# Feinstaubsensor_w.net
KiCad netlist of a schematic drawn in EAGLE
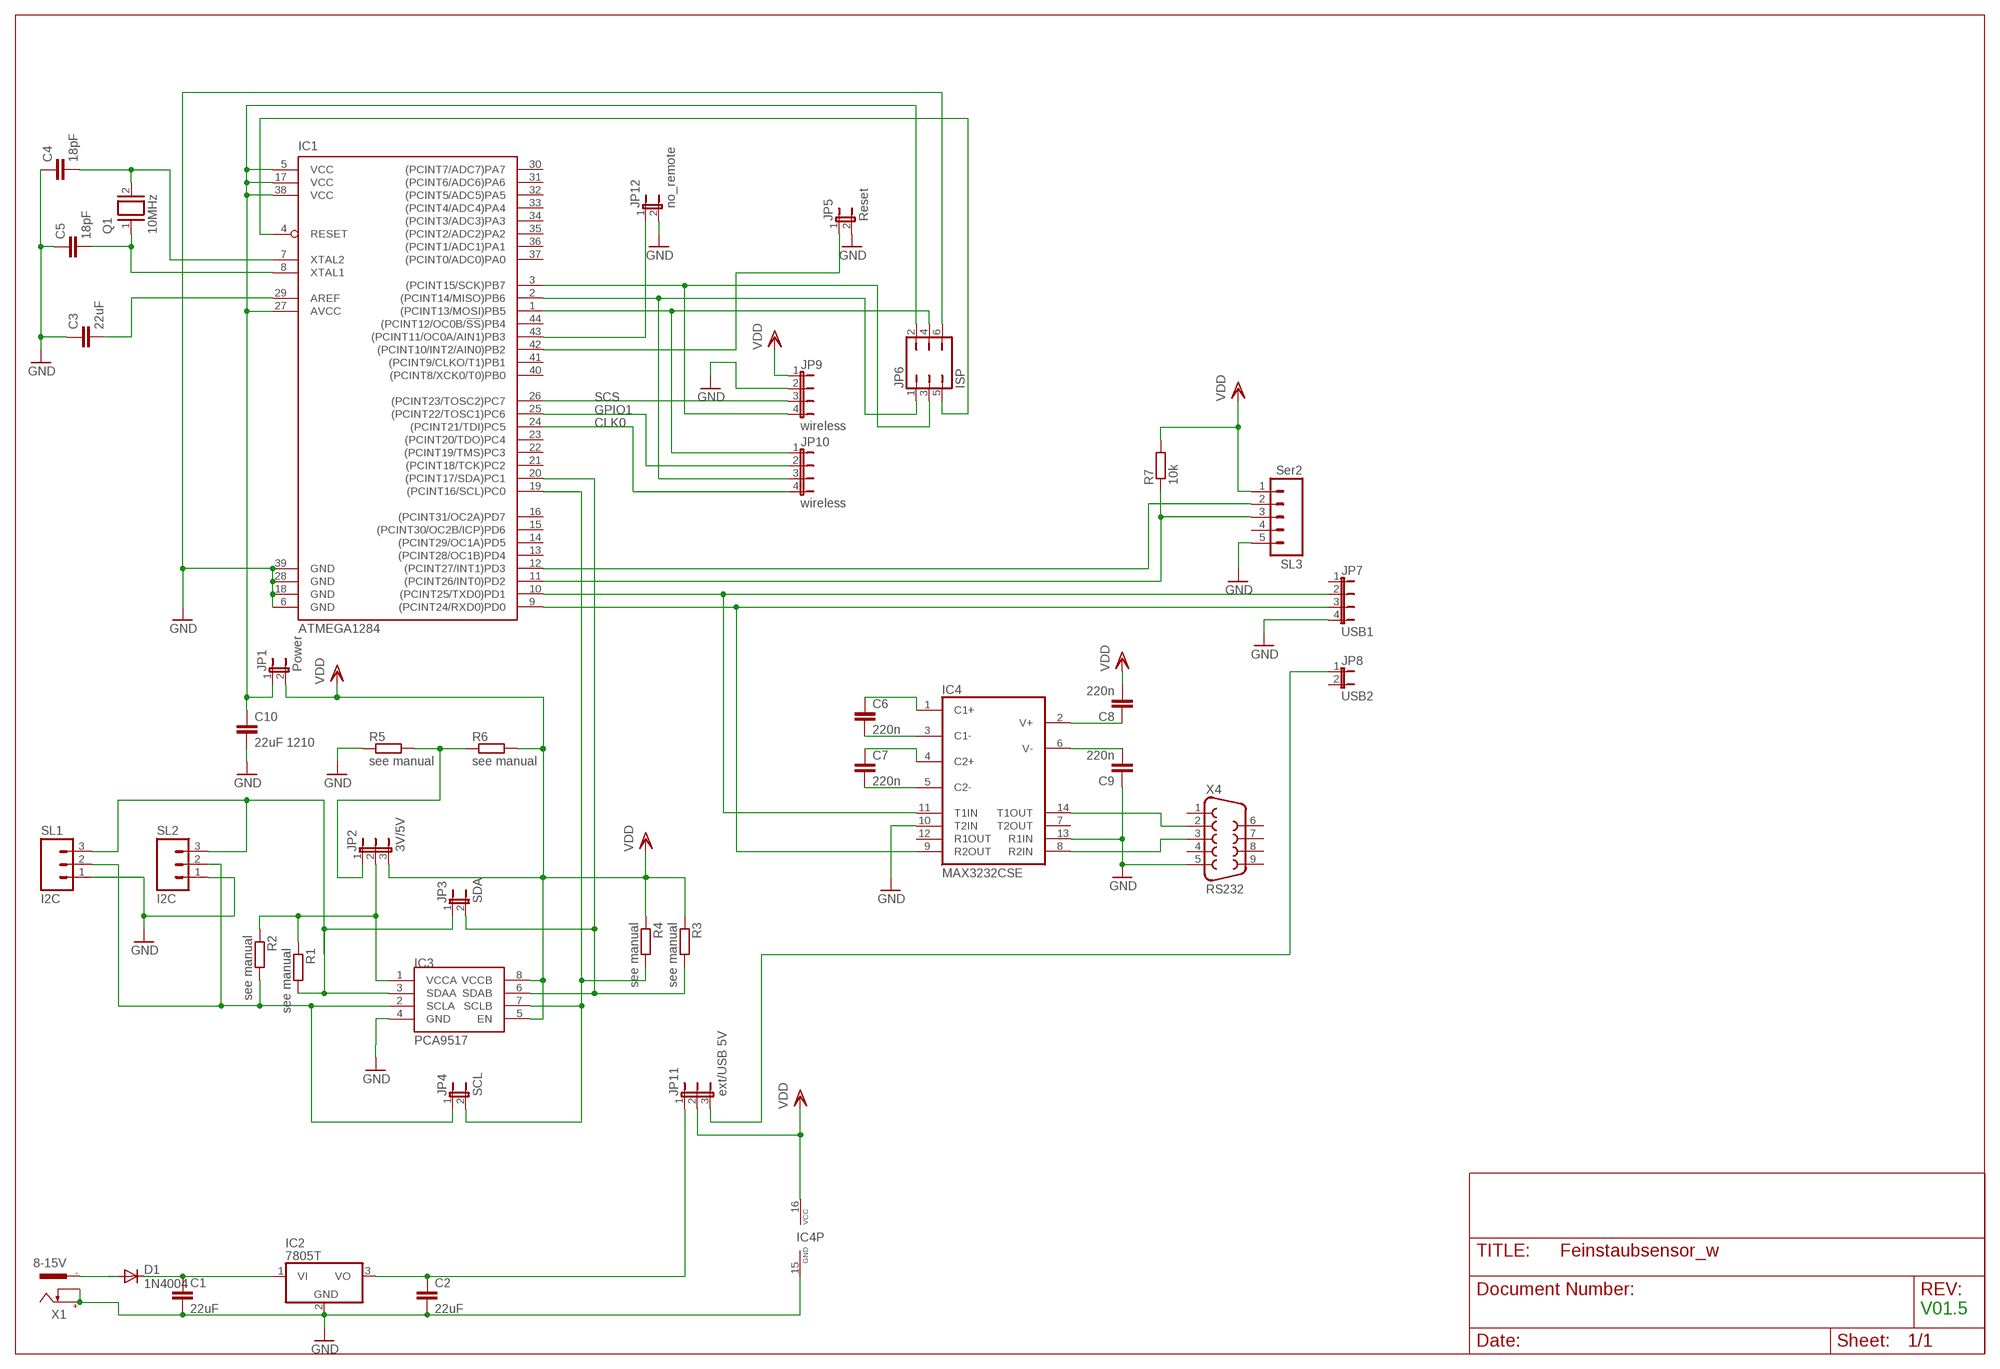
[diagram p0: schematic, sheet 1]

(export (version "E")
  (design (tool "Eeschema 10.0.6"))
  (components
    (comp (ref "C1")
      (value "22uF")
      (footprint "eagle-import:C1206")
      (libsource (lib "eagle-import") (part "C-EUC1206"))
    )
    (comp (ref "C2")
      (value "22uF")
      (footprint "eagle-import:C1206")
      (libsource (lib "eagle-import") (part "C-EUC1206"))
    )
    (comp (ref "C3")
      (value "22uF")
      (footprint "eagle-import:C1206")
      (libsource (lib "eagle-import") (part "C-EUC1206"))
    )
    (comp (ref "C4")
      (value "18pF")
      (footprint "eagle-import:C025-025X050")
      (libsource (lib "eagle-import") (part "resistor_C-EU025-025X050"))
    )
    (comp (ref "C5")
      (value "18pF")
      (footprint "eagle-import:C025-025X050")
      (libsource (lib "eagle-import") (part "resistor_C-EU025-025X050"))
    )
    (comp (ref "C6")
      (value "220n")
      (footprint "eagle-import:C1206")
      (libsource (lib "eagle-import") (part "C-EUC1206"))
    )
    (comp (ref "C7")
      (value "220n")
      (footprint "eagle-import:C1206")
      (libsource (lib "eagle-import") (part "C-EUC1206"))
    )
    (comp (ref "C8")
      (value "220n")
      (footprint "eagle-import:C1206")
      (libsource (lib "eagle-import") (part "C-EUC1206"))
    )
    (comp (ref "C9")
      (value "220n")
      (footprint "eagle-import:C1206")
      (libsource (lib "eagle-import") (part "C-EUC1206"))
    )
    (comp (ref "C10")
      (value "22uF 1210")
      (footprint "eagle-import:C1206")
      (libsource (lib "eagle-import") (part "C-EUC1206"))
    )
    (comp (ref "D1")
      (value "1N4004")
      (footprint "eagle-import:DO41-10")
      (libsource (lib "eagle-import") (part "1N4004"))
    )
    (comp (ref "IC1")
      (value "ATMEGA1284")
      (footprint "eagle-import:TQFP44")
      (fields (field (name "MPN") "ATMEGA644PV-10AU"))
      (libsource (lib "eagle-import") (part "ATMEGA644A"))
    )
    (comp (ref "IC2")
      (value "7805T")
      (footprint "eagle-import:TO220H")
      (libsource (lib "eagle-import") (part "78T05"))
    )
    (comp (ref "IC3")
      (value "PCA9517")
      (footprint "eagle-import:SO-08")
      (libsource (lib "eagle-import") (part "PCA9517"))
    )
    (comp (ref "IC4")
      (value "MAX3232CSE")
      (footprint "eagle-import:SO16")
      (libsource (lib "eagle-import") (part "MAX3232SEC"))
    )
    (comp (ref "JP1")
      (value "Power")
      (footprint "eagle-import:JP1")
      (libsource (lib "eagle-import") (part "JP1E"))
    )
    (comp (ref "JP2")
      (value "3V/5V")
      (footprint "eagle-import:JP2")
      (libsource (lib "eagle-import") (part "JP2E"))
    )
    (comp (ref "JP3")
      (value "SDA")
      (footprint "eagle-import:JP1")
      (libsource (lib "eagle-import") (part "JP1E"))
    )
    (comp (ref "JP4")
      (value "SCL")
      (footprint "eagle-import:JP1")
      (libsource (lib "eagle-import") (part "JP1E"))
    )
    (comp (ref "JP5")
      (value "Reset")
      (footprint "eagle-import:JP1")
      (libsource (lib "eagle-import") (part "JP1E"))
    )
    (comp (ref "JP6")
      (value "ISP")
      (footprint "eagle-import:JP3Q")
      (libsource (lib "eagle-import") (part "JP3Q"))
    )
    (comp (ref "JP7")
      (value "USB1")
      (footprint "eagle-import:JP4")
      (libsource (lib "eagle-import") (part "JP4E"))
    )
    (comp (ref "JP8")
      (value "USB2")
      (footprint "eagle-import:JP1")
      (libsource (lib "eagle-import") (part "JP1E"))
    )
    (comp (ref "JP9")
      (value "wireless")
      (footprint "eagle-import:JP4")
      (libsource (lib "eagle-import") (part "JP4E"))
    )
    (comp (ref "JP10")
      (value "wireless")
      (footprint "eagle-import:JP4")
      (libsource (lib "eagle-import") (part "JP4E"))
    )
    (comp (ref "JP11")
      (value "ext/USB 5V")
      (footprint "eagle-import:JP2")
      (libsource (lib "eagle-import") (part "JP2E"))
    )
    (comp (ref "JP12")
      (value "no_remote")
      (footprint "eagle-import:JP1")
      (libsource (lib "eagle-import") (part "JP1E"))
    )
    (comp (ref "Q1")
      (value "10MHz")
      (footprint "eagle-import:QS")
      (libsource (lib "eagle-import") (part "XTAL/S"))
    )
    (comp (ref "R1")
      (value "see manual")
      (footprint "eagle-import:R1206")
      (libsource (lib "eagle-import") (part "R-EU_R1206"))
    )
    (comp (ref "R2")
      (value "see manual")
      (footprint "eagle-import:R1206")
      (libsource (lib "eagle-import") (part "R-EU_R1206"))
    )
    (comp (ref "R3")
      (value "see manual")
      (footprint "eagle-import:R1206")
      (libsource (lib "eagle-import") (part "R-EU_R1206"))
    )
    (comp (ref "R4")
      (value "see manual")
      (footprint "eagle-import:R1206")
      (libsource (lib "eagle-import") (part "R-EU_R1206"))
    )
    (comp (ref "R5")
      (value "see manual")
      (footprint "eagle-import:R1206")
      (libsource (lib "eagle-import") (part "R-EU_R1206"))
    )
    (comp (ref "R6")
      (value "see manual")
      (footprint "eagle-import:R1206")
      (libsource (lib "eagle-import") (part "R-EU_R1206"))
    )
    (comp (ref "R7")
      (value "10k")
      (footprint "eagle-import:R1206")
      (libsource (lib "eagle-import") (part "R-EU_R1206"))
    )
    (comp (ref "SL1")
      (value "I2C")
      (footprint "eagle-import:03P")
      (libsource (lib "eagle-import") (part "M03"))
    )
    (comp (ref "SL2")
      (value "I2C")
      (footprint "eagle-import:03P")
      (libsource (lib "eagle-import") (part "M03"))
    )
    (comp (ref "SL3")
      (value "Ser2")
      (footprint "eagle-import:05P")
      (libsource (lib "eagle-import") (part "M05"))
    )
    (comp (ref "X1")
      (value "8-15V")
      (footprint "eagle-import:737992-5")
      (libsource (lib "eagle-import") (part "737992-55"))
    )
    (comp (ref "X4")
      (value "RS232")
      (footprint "eagle-import:F09H")
      (libsource (lib "eagle-import") (part "F09H"))
    )
  )
  (nets
    (net (code "1") (name "/CLK0") (class "Default")
      (node (ref "IC1") (pin "24") (pinfunction "(PCINT21/TDI)PC5_24") (pintype "output"))
      (node (ref "JP10") (pin "4") (pinfunction "4_4") (pintype "passive"))
    )
    (net (code "2") (name "/GPIO1") (class "Default")
      (node (ref "IC1") (pin "25") (pinfunction "(PCINT22/TOSC1)PC6_25") (pintype "output"))
      (node (ref "JP10") (pin "2") (pinfunction "2_2") (pintype "passive"))
    )
    (net (code "3") (name "/SCS") (class "Default")
      (node (ref "IC1") (pin "26") (pinfunction "(PCINT23/TOSC2)PC7_26") (pintype "output"))
      (node (ref "JP9") (pin "3") (pinfunction "3_3") (pintype "passive"))
    )
    (net (code "4") (name "GND") (class "Default")
      (node (ref "C1") (pin "2") (pinfunction "2_2") (pintype "passive"))
      (node (ref "C10") (pin "2") (pinfunction "2_2") (pintype "passive"))
      (node (ref "C2") (pin "2") (pinfunction "2_2") (pintype "passive"))
      (node (ref "C3") (pin "1") (pinfunction "1_1") (pintype "passive"))
      (node (ref "C4") (pin "1") (pinfunction "1_1") (pintype "passive"))
      (node (ref "C5") (pin "1") (pinfunction "1_1") (pintype "passive"))
      (node (ref "C9") (pin "1") (pinfunction "1_1") (pintype "passive"))
      (node (ref "IC1") (pin "18") (pinfunction "GND_18") (pintype "power_in"))
      (node (ref "IC1") (pin "28") (pinfunction "GND_28") (pintype "power_in"))
      (node (ref "IC1") (pin "39") (pinfunction "GND_39") (pintype "power_in"))
      (node (ref "IC1") (pin "6") (pinfunction "GND_6") (pintype "power_in"))
      (node (ref "IC2") (pin "2") (pinfunction "GND_2") (pintype "passive"))
      (node (ref "IC3") (pin "4") (pinfunction "GND_4") (pintype "bidirectional"))
      (node (ref "IC4") (pin "10") (pinfunction "T2IN_10") (pintype "input"))
      (node (ref "IC4") (pin "13") (pinfunction "R1IN_13") (pintype "input"))
      (node (ref "IC4") (pin "15") (pinfunction "GND_15") (pintype "power_in"))
      (node (ref "JP12") (pin "2") (pinfunction "2_2") (pintype "passive"))
      (node (ref "JP5") (pin "2") (pinfunction "2_2") (pintype "passive"))
      (node (ref "JP6") (pin "6") (pinfunction "6_6") (pintype "passive"))
      (node (ref "JP7") (pin "4") (pinfunction "4_4") (pintype "passive"))
      (node (ref "JP9") (pin "2") (pinfunction "2_2") (pintype "passive"))
      (node (ref "R5") (pin "1") (pinfunction "1_1") (pintype "passive"))
      (node (ref "SL1") (pin "1") (pinfunction "1_1") (pintype "passive"))
      (node (ref "SL2") (pin "1") (pinfunction "1_1") (pintype "passive"))
      (node (ref "SL3") (pin "5") (pinfunction "5_5") (pintype "passive"))
      (node (ref "X1") (pin "+") (pinfunction "+_+") (pintype "passive"))
      (node (ref "X1") (pin "K") (pinfunction "K_K") (pintype "passive"))
      (node (ref "X4") (pin "5") (pinfunction "5_5") (pintype "passive"))
    )
    (net (code "5") (name "Net-(D1-PadA)") (class "Default")
      (node (ref "D1") (pin "A") (pinfunction "A_A") (pintype "passive"))
      (node (ref "X1") (pin "-1") (pinfunction "-1_-1") (pintype "passive"))
    )
    (net (code "6") (name "Net-(IC1-(PCINT10{slash}INT2{slash}AIN0)PB2)") (class "Default")
      (node (ref "IC1") (pin "42") (pinfunction "(PCINT10/INT2/AIN0)PB2_42") (pintype "bidirectional"))
      (node (ref "JP5") (pin "1") (pinfunction "1_1") (pintype "passive"))
    )
    (net (code "7") (name "Net-(IC1-(PCINT11{slash}OC0A{slash}AIN1)PB3)") (class "Default")
      (node (ref "IC1") (pin "43") (pinfunction "(PCINT11/OC0A/AIN1)PB3_43") (pintype "bidirectional"))
      (node (ref "JP12") (pin "1") (pinfunction "1_1") (pintype "passive"))
    )
    (net (code "8") (name "Net-(IC1-(PCINT13{slash}MOSI)PB5)") (class "Default")
      (node (ref "IC1") (pin "1") (pinfunction "(PCINT13/MOSI)PB5_1") (pintype "bidirectional"))
      (node (ref "JP10") (pin "1") (pinfunction "1_1") (pintype "passive"))
      (node (ref "JP6") (pin "4") (pinfunction "4_4") (pintype "passive"))
    )
    (net (code "9") (name "Net-(IC1-(PCINT14{slash}MISO)PB6)") (class "Default")
      (node (ref "IC1") (pin "2") (pinfunction "(PCINT14/MISO)PB6_2") (pintype "bidirectional"))
      (node (ref "JP10") (pin "3") (pinfunction "3_3") (pintype "passive"))
      (node (ref "JP6") (pin "1") (pinfunction "1_1") (pintype "passive"))
    )
    (net (code "10") (name "Net-(IC1-(PCINT15{slash}SCK)PB7)") (class "Default")
      (node (ref "IC1") (pin "3") (pinfunction "(PCINT15/SCK)PB7_3") (pintype "bidirectional"))
      (node (ref "JP6") (pin "3") (pinfunction "3_3") (pintype "passive"))
      (node (ref "JP9") (pin "4") (pinfunction "4_4") (pintype "passive"))
    )
    (net (code "11") (name "Net-(IC1-(PCINT16{slash}SCL)PC0)") (class "Default")
      (node (ref "IC1") (pin "19") (pinfunction "(PCINT16/SCL)PC0_19") (pintype "output"))
      (node (ref "IC3") (pin "7") (pinfunction "SCLB_7") (pintype "bidirectional"))
      (node (ref "JP4") (pin "2") (pinfunction "2_2") (pintype "passive"))
      (node (ref "R4") (pin "2") (pinfunction "2_2") (pintype "passive"))
    )
    (net (code "12") (name "Net-(IC1-(PCINT17{slash}SDA)PC1)") (class "Default")
      (node (ref "IC1") (pin "20") (pinfunction "(PCINT17/SDA)PC1_20") (pintype "output"))
      (node (ref "IC3") (pin "6") (pinfunction "SDAB_6") (pintype "bidirectional"))
      (node (ref "JP3") (pin "2") (pinfunction "2_2") (pintype "passive"))
      (node (ref "R3") (pin "2") (pinfunction "2_2") (pintype "passive"))
    )
    (net (code "13") (name "Net-(IC1-(PCINT24{slash}RXD0)PD0)") (class "Default")
      (node (ref "IC1") (pin "9") (pinfunction "(PCINT24/RXD0)PD0_9") (pintype "bidirectional"))
      (node (ref "IC4") (pin "9") (pinfunction "R2OUT_9") (pintype "output"))
      (node (ref "JP7") (pin "3") (pinfunction "3_3") (pintype "passive"))
    )
    (net (code "14") (name "Net-(IC1-(PCINT25{slash}TXD0)PD1)") (class "Default")
      (node (ref "IC1") (pin "10") (pinfunction "(PCINT25/TXD0)PD1_10") (pintype "bidirectional"))
      (node (ref "IC4") (pin "11") (pinfunction "T1IN_11") (pintype "input"))
      (node (ref "JP7") (pin "2") (pinfunction "2_2") (pintype "passive"))
    )
    (net (code "15") (name "Net-(IC1-(PCINT26{slash}INT0)PD2)") (class "Default")
      (node (ref "IC1") (pin "11") (pinfunction "(PCINT26/INT0)PD2_11") (pintype "bidirectional"))
      (node (ref "R7") (pin "1") (pinfunction "1_1") (pintype "passive"))
      (node (ref "SL3") (pin "3") (pinfunction "3_3") (pintype "passive"))
    )
    (net (code "16") (name "Net-(IC1-(PCINT27{slash}INT1)PD3)") (class "Default")
      (node (ref "IC1") (pin "12") (pinfunction "(PCINT27/INT1)PD3_12") (pintype "bidirectional"))
      (node (ref "SL3") (pin "2") (pinfunction "2_2") (pintype "passive"))
    )
    (net (code "17") (name "Net-(IC1-AREF)") (class "Default")
      (node (ref "C3") (pin "2") (pinfunction "2_2") (pintype "passive"))
      (node (ref "IC1") (pin "29") (pinfunction "AREF_29") (pintype "passive"))
    )
    (net (code "18") (name "Net-(IC1-AVCC)") (class "Default")
      (node (ref "C10") (pin "1") (pinfunction "1_1") (pintype "passive"))
      (node (ref "IC1") (pin "17") (pinfunction "VCC_17") (pintype "power_in"))
      (node (ref "IC1") (pin "27") (pinfunction "AVCC_27") (pintype "power_in"))
      (node (ref "IC1") (pin "38") (pinfunction "VCC_38") (pintype "power_in"))
      (node (ref "IC1") (pin "5") (pinfunction "VCC_5") (pintype "power_in"))
      (node (ref "JP1") (pin "1") (pinfunction "1_1") (pintype "passive"))
      (node (ref "JP6") (pin "2") (pinfunction "2_2") (pintype "passive"))
    )
    (net (code "19") (name "Net-(IC1-RESET)") (class "Default")
      (node (ref "IC1") (pin "4") (pinfunction "RESET_4") (pintype "input"))
      (node (ref "JP6") (pin "5") (pinfunction "5_5") (pintype "passive"))
    )
    (net (code "20") (name "Net-(IC1-XTAL1)") (class "Default")
      (node (ref "C5") (pin "2") (pinfunction "2_2") (pintype "passive"))
      (node (ref "IC1") (pin "8") (pinfunction "XTAL1_8") (pintype "bidirectional"))
      (node (ref "Q1") (pin "1") (pinfunction "1_1") (pintype "passive"))
    )
    (net (code "21") (name "Net-(IC1-XTAL2)") (class "Default")
      (node (ref "C4") (pin "2") (pinfunction "2_2") (pintype "passive"))
      (node (ref "IC1") (pin "7") (pinfunction "XTAL2_7") (pintype "bidirectional"))
      (node (ref "Q1") (pin "2") (pinfunction "2_2") (pintype "passive"))
    )
    (net (code "22") (name "Net-(IC2-VI)") (class "Default")
      (node (ref "C1") (pin "1") (pinfunction "1_1") (pintype "passive"))
      (node (ref "D1") (pin "C") (pinfunction "C_C") (pintype "passive"))
      (node (ref "IC2") (pin "1") (pinfunction "VI_1") (pintype "input"))
    )
    (net (code "23") (name "Net-(IC2-VO)") (class "Default")
      (node (ref "C2") (pin "1") (pinfunction "1_1") (pintype "passive"))
      (node (ref "IC2") (pin "3") (pinfunction "VO_3") (pintype "passive"))
      (node (ref "JP11") (pin "1") (pinfunction "1_1") (pintype "passive"))
    )
    (net (code "24") (name "Net-(IC3-SCLA)") (class "Default")
      (node (ref "IC3") (pin "2") (pinfunction "SCLA_2") (pintype "bidirectional"))
      (node (ref "JP4") (pin "1") (pinfunction "1_1") (pintype "passive"))
      (node (ref "R2") (pin "2") (pinfunction "2_2") (pintype "passive"))
      (node (ref "SL1") (pin "2") (pinfunction "2_2") (pintype "passive"))
      (node (ref "SL2") (pin "2") (pinfunction "2_2") (pintype "passive"))
    )
    (net (code "25") (name "Net-(IC3-SDAA)") (class "Default")
      (node (ref "IC3") (pin "3") (pinfunction "SDAA_3") (pintype "bidirectional"))
      (node (ref "JP3") (pin "1") (pinfunction "1_1") (pintype "passive"))
      (node (ref "R1") (pin "2") (pinfunction "2_2") (pintype "passive"))
      (node (ref "SL1") (pin "3") (pinfunction "3_3") (pintype "passive"))
      (node (ref "SL2") (pin "3") (pinfunction "3_3") (pintype "passive"))
    )
    (net (code "26") (name "Net-(IC3-VCCA)") (class "Default")
      (node (ref "IC3") (pin "1") (pinfunction "VCCA_1") (pintype "bidirectional"))
      (node (ref "JP2") (pin "2") (pinfunction "2_2") (pintype "passive"))
      (node (ref "R1") (pin "1") (pinfunction "1_1") (pintype "passive"))
      (node (ref "R2") (pin "1") (pinfunction "1_1") (pintype "passive"))
    )
    (net (code "27") (name "Net-(IC4A-C1+)") (class "Default")
      (node (ref "C6") (pin "1") (pinfunction "1_1") (pintype "passive"))
      (node (ref "IC4") (pin "1") (pinfunction "C1+_1") (pintype "bidirectional"))
    )
    (net (code "28") (name "Net-(IC4A-C1-)") (class "Default")
      (node (ref "C6") (pin "2") (pinfunction "2_2") (pintype "passive"))
      (node (ref "IC4") (pin "3") (pinfunction "C1-_3") (pintype "bidirectional"))
    )
    (net (code "29") (name "Net-(IC4A-C2+)") (class "Default")
      (node (ref "C7") (pin "1") (pinfunction "1_1") (pintype "passive"))
      (node (ref "IC4") (pin "4") (pinfunction "C2+_4") (pintype "bidirectional"))
    )
    (net (code "30") (name "Net-(IC4A-C2-)") (class "Default")
      (node (ref "C7") (pin "2") (pinfunction "2_2") (pintype "passive"))
      (node (ref "IC4") (pin "5") (pinfunction "C2-_5") (pintype "bidirectional"))
    )
    (net (code "31") (name "Net-(IC4A-R2IN)") (class "Default")
      (node (ref "IC4") (pin "8") (pinfunction "R2IN_8") (pintype "input"))
      (node (ref "X4") (pin "3") (pinfunction "3_3") (pintype "passive"))
    )
    (net (code "32") (name "Net-(IC4A-T1OUT)") (class "Default")
      (node (ref "IC4") (pin "14") (pinfunction "T1OUT_14") (pintype "output"))
      (node (ref "X4") (pin "2") (pinfunction "2_2") (pintype "passive"))
    )
    (net (code "33") (name "Net-(IC4A-V+)") (class "Default")
      (node (ref "C8") (pin "1") (pinfunction "1_1") (pintype "passive"))
      (node (ref "IC4") (pin "2") (pinfunction "V+_2") (pintype "bidirectional"))
    )
    (net (code "34") (name "Net-(IC4A-V-)") (class "Default")
      (node (ref "C9") (pin "2") (pinfunction "2_2") (pintype "passive"))
      (node (ref "IC4") (pin "6") (pinfunction "V-_6") (pintype "bidirectional"))
    )
    (net (code "35") (name "Net-(JP2-Pad1)") (class "Default")
      (node (ref "JP2") (pin "1") (pinfunction "1_1") (pintype "passive"))
      (node (ref "R5") (pin "2") (pinfunction "2_2") (pintype "passive"))
      (node (ref "R6") (pin "1") (pinfunction "1_1") (pintype "passive"))
    )
    (net (code "36") (name "Net-(JP11-Pad3)") (class "Default")
      (node (ref "JP11") (pin "3") (pinfunction "3_3") (pintype "passive"))
      (node (ref "JP8") (pin "1") (pinfunction "1_1") (pintype "passive"))
    )
    (net (code "37") (name "VDD") (class "Default")
      (node (ref "C8") (pin "2") (pinfunction "2_2") (pintype "passive"))
      (node (ref "IC3") (pin "5") (pinfunction "EN_5") (pintype "bidirectional"))
      (node (ref "IC3") (pin "8") (pinfunction "VCCB_8") (pintype "bidirectional"))
      (node (ref "IC4") (pin "16") (pinfunction "VCC_16") (pintype "power_in"))
      (node (ref "JP1") (pin "2") (pinfunction "2_2") (pintype "passive"))
      (node (ref "JP11") (pin "2") (pinfunction "2_2") (pintype "passive"))
      (node (ref "JP2") (pin "3") (pinfunction "3_3") (pintype "passive"))
      (node (ref "JP9") (pin "1") (pinfunction "1_1") (pintype "passive"))
      (node (ref "R3") (pin "1") (pinfunction "1_1") (pintype "passive"))
      (node (ref "R4") (pin "1") (pinfunction "1_1") (pintype "passive"))
      (node (ref "R6") (pin "2") (pinfunction "2_2") (pintype "passive"))
      (node (ref "R7") (pin "2") (pinfunction "2_2") (pintype "passive"))
      (node (ref "SL3") (pin "1") (pinfunction "1_1") (pintype "passive"))
    )
    (net (code "38") (name "unconnected-(IC1-(PCINT0{slash}ADC0)PA0-Pad37)") (class "Default")
      (node (ref "IC1") (pin "37") (pinfunction "(PCINT0/ADC0)PA0_37") (pintype "bidirectional"))
    )
    (net (code "39") (name "unconnected-(IC1-(PCINT1{slash}ADC1)PA1-Pad36)") (class "Default")
      (node (ref "IC1") (pin "36") (pinfunction "(PCINT1/ADC1)PA1_36") (pintype "bidirectional"))
    )
    (net (code "40") (name "unconnected-(IC1-(PCINT2{slash}ADC2)PA2-Pad35)") (class "Default")
      (node (ref "IC1") (pin "35") (pinfunction "(PCINT2/ADC2)PA2_35") (pintype "bidirectional"))
    )
    (net (code "41") (name "unconnected-(IC1-(PCINT3{slash}ADC3)PA3-Pad34)") (class "Default")
      (node (ref "IC1") (pin "34") (pinfunction "(PCINT3/ADC3)PA3_34") (pintype "bidirectional"))
    )
    (net (code "42") (name "unconnected-(IC1-(PCINT4{slash}ADC4)PA4-Pad33)") (class "Default")
      (node (ref "IC1") (pin "33") (pinfunction "(PCINT4/ADC4)PA4_33") (pintype "bidirectional"))
    )
    (net (code "43") (name "unconnected-(IC1-(PCINT5{slash}ADC5)PA5-Pad32)") (class "Default")
      (node (ref "IC1") (pin "32") (pinfunction "(PCINT5/ADC5)PA5_32") (pintype "bidirectional"))
    )
    (net (code "44") (name "unconnected-(IC1-(PCINT6{slash}ADC6)PA6-Pad31)") (class "Default")
      (node (ref "IC1") (pin "31") (pinfunction "(PCINT6/ADC6)PA6_31") (pintype "bidirectional"))
    )
    (net (code "45") (name "unconnected-(IC1-(PCINT7{slash}ADC7)PA7-Pad30)") (class "Default")
      (node (ref "IC1") (pin "30") (pinfunction "(PCINT7/ADC7)PA7_30") (pintype "bidirectional"))
    )
    (net (code "46") (name "unconnected-(IC1-(PCINT8{slash}XCK0{slash}T0)PB0-Pad40)") (class "Default")
      (node (ref "IC1") (pin "40") (pinfunction "(PCINT8/XCK0/T0)PB0_40") (pintype "bidirectional"))
    )
    (net (code "47") (name "unconnected-(IC1-(PCINT9{slash}CLKO{slash}T1)PB1-Pad41)") (class "Default")
      (node (ref "IC1") (pin "41") (pinfunction "(PCINT9/CLKO/T1)PB1_41") (pintype "bidirectional"))
    )
    (net (code "48") (name "unconnected-(IC1-(PCINT12{slash}OC0B{slash}~{SS})PB4-Pad44)") (class "Default")
      (node (ref "IC1") (pin "44") (pinfunction "(PCINT12/OC0B/~{SS})PB4_44") (pintype "bidirectional"))
    )
    (net (code "49") (name "unconnected-(IC1-(PCINT18{slash}TCK)PC2-Pad21)") (class "Default")
      (node (ref "IC1") (pin "21") (pinfunction "(PCINT18/TCK)PC2_21") (pintype "output"))
    )
    (net (code "50") (name "unconnected-(IC1-(PCINT19{slash}TMS)PC3-Pad22)") (class "Default")
      (node (ref "IC1") (pin "22") (pinfunction "(PCINT19/TMS)PC3_22") (pintype "output"))
    )
    (net (code "51") (name "unconnected-(IC1-(PCINT20{slash}TDO)PC4-Pad23)") (class "Default")
      (node (ref "IC1") (pin "23") (pinfunction "(PCINT20/TDO)PC4_23") (pintype "output"))
    )
    (net (code "52") (name "unconnected-(IC1-(PCINT28{slash}OC1B)PD4-Pad13)") (class "Default")
      (node (ref "IC1") (pin "13") (pinfunction "(PCINT28/OC1B)PD4_13") (pintype "bidirectional"))
    )
    (net (code "53") (name "unconnected-(IC1-(PCINT29{slash}OC1A)PD5-Pad14)") (class "Default")
      (node (ref "IC1") (pin "14") (pinfunction "(PCINT29/OC1A)PD5_14") (pintype "bidirectional"))
    )
    (net (code "54") (name "unconnected-(IC1-(PCINT30{slash}OC2B{slash}ICP)PD6-Pad15)") (class "Default")
      (node (ref "IC1") (pin "15") (pinfunction "(PCINT30/OC2B/ICP)PD6_15") (pintype "bidirectional"))
    )
    (net (code "55") (name "unconnected-(IC1-(PCINT31{slash}OC2A)PD7-Pad16)") (class "Default")
      (node (ref "IC1") (pin "16") (pinfunction "(PCINT31/OC2A)PD7_16") (pintype "bidirectional"))
    )
    (net (code "56") (name "unconnected-(IC4A-R1OUT-Pad12)") (class "Default")
      (node (ref "IC4") (pin "12") (pinfunction "R1OUT_12") (pintype "output"))
    )
    (net (code "57") (name "unconnected-(IC4A-T2OUT-Pad7)") (class "Default")
      (node (ref "IC4") (pin "7") (pinfunction "T2OUT_7") (pintype "output"))
    )
    (net (code "58") (name "unconnected-(JP7-Pad1)") (class "Default")
      (node (ref "JP7") (pin "1") (pinfunction "1_1") (pintype "passive"))
    )
    (net (code "59") (name "unconnected-(JP8-Pad2)") (class "Default")
      (node (ref "JP8") (pin "2") (pinfunction "2_2") (pintype "passive"))
    )
    (net (code "60") (name "unconnected-(SL3-Pad4)") (class "Default")
      (node (ref "SL3") (pin "4") (pinfunction "4_4") (pintype "passive"))
    )
    (net (code "61") (name "unconnected-(X1-Pad-2)") (class "Default")
      (node (ref "X1") (pin "-2") (pinfunction "-2_-2") (pintype "passive"))
    )
    (net (code "62") (name "unconnected-(X4-Pad1)") (class "Default")
      (node (ref "X4") (pin "1") (pinfunction "1_1") (pintype "passive"))
    )
    (net (code "63") (name "unconnected-(X4-Pad4)") (class "Default")
      (node (ref "X4") (pin "4") (pinfunction "4_4") (pintype "passive"))
    )
    (net (code "64") (name "unconnected-(X4-Pad6)") (class "Default")
      (node (ref "X4") (pin "6") (pinfunction "6_6") (pintype "passive"))
    )
    (net (code "65") (name "unconnected-(X4-Pad7)") (class "Default")
      (node (ref "X4") (pin "7") (pinfunction "7_7") (pintype "passive"))
    )
    (net (code "66") (name "unconnected-(X4-Pad8)") (class "Default")
      (node (ref "X4") (pin "8") (pinfunction "8_8") (pintype "passive"))
    )
    (net (code "67") (name "unconnected-(X4-Pad9)") (class "Default")
      (node (ref "X4") (pin "9") (pinfunction "9_9") (pintype "passive"))
    )
  )
)
